# ECG_NEMO_final_V1B_main_stack2.net
KiCad netlist of a schematic drawn in Altium Designer
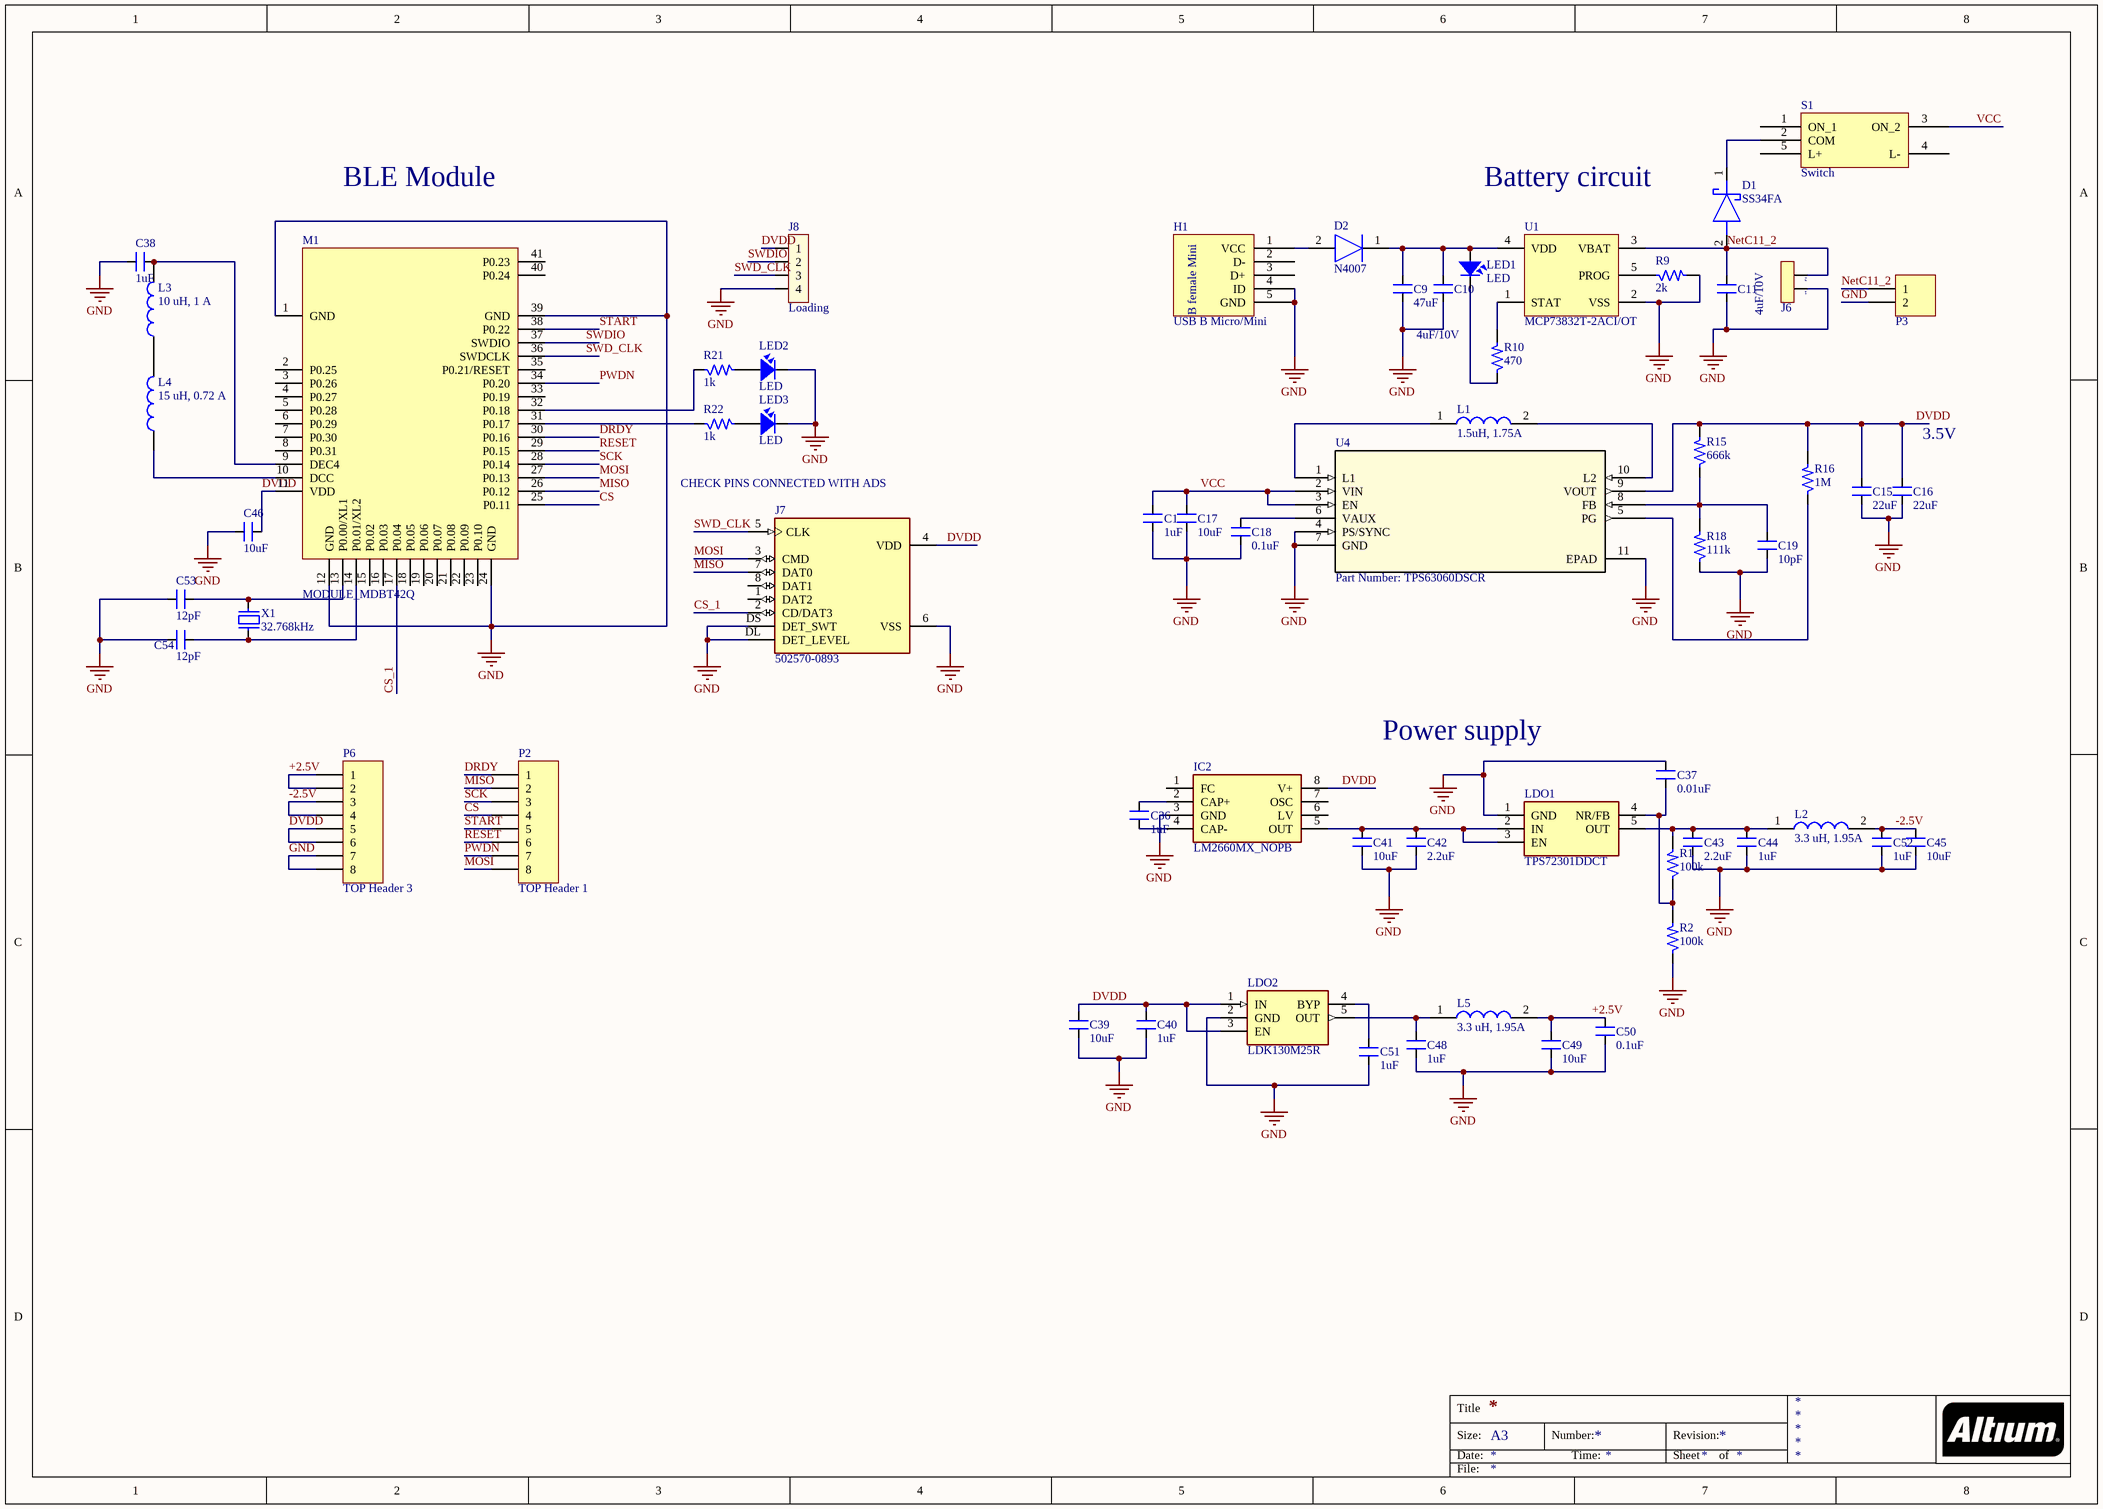
[diagram p0: ECG_NEMO_final_V1B_main_stack2.schdoc]

(export (version "E")
  (design (tool "Eeschema 10.0.6"))
  (components
    (comp (ref "C1")
      (value "1uF")
      (footprint "SM-0805")
      (description "Cap SMD")
      (libsource (lib "VioletofSun") (part "CM"))
    )
    (comp (ref "C9")
      (value "47uF")
      (footprint "SM-0805")
      (description "Cap SMD")
      (libsource (lib "VioletofSun") (part "CM"))
    )
    (comp (ref "C10")
      (value "4uF/10V")
      (footprint "SM-0805")
      (description "Cap SMD")
      (libsource (lib "VioletofSun") (part "CM"))
    )
    (comp (ref "C11")
      (value "4uF/10V")
      (footprint "SM-0805")
      (description "Cap SMD")
      (libsource (lib "VioletofSun") (part "CM"))
    )
    (comp (ref "C15")
      (value "22uF")
      (footprint "SM-0805")
      (description "Cap SMD")
      (libsource (lib "VioletofSun") (part "CM"))
    )
    (comp (ref "C16")
      (value "22uF")
      (footprint "SM-0805")
      (description "Cap SMD")
      (libsource (lib "VioletofSun") (part "CM"))
    )
    (comp (ref "C17")
      (value "10uF")
      (footprint "SM-0805")
      (description "Cap SMD")
      (libsource (lib "VioletofSun") (part "CM"))
    )
    (comp (ref "C18")
      (value "0.1uF")
      (footprint "SM-0805")
      (description "Cap SMD")
      (libsource (lib "VioletofSun") (part "CM"))
    )
    (comp (ref "C19")
      (value "10pF")
      (footprint "SM-0805")
      (description "Cap SMD")
      (libsource (lib "VioletofSun") (part "CM"))
    )
    (comp (ref "C36")
      (value "1uF")
      (footprint "SM-0805")
      (description "Cap SMD")
      (libsource (lib "VioletofSun") (part "CM"))
    )
    (comp (ref "C37")
      (value "0.01uF")
      (footprint "SM-0805")
      (description "Cap SMD")
      (libsource (lib "VioletofSun") (part "CM"))
    )
    (comp (ref "C38")
      (value "1uF")
      (footprint "SM-0805")
      (description "Cap SMD")
      (libsource (lib "VioletofSun") (part "CM"))
    )
    (comp (ref "C39")
      (value "10uF")
      (footprint "SM-0805")
      (description "Cap SMD")
      (libsource (lib "VioletofSun") (part "CM"))
    )
    (comp (ref "C40")
      (value "1uF")
      (footprint "SM-0805")
      (description "Cap SMD")
      (libsource (lib "VioletofSun") (part "CM"))
    )
    (comp (ref "C41")
      (value "10uF")
      (footprint "SM-0805")
      (description "Cap SMD")
      (libsource (lib "VioletofSun") (part "CM"))
    )
    (comp (ref "C42")
      (value "2.2uF")
      (footprint "SM-0805")
      (description "Cap SMD")
      (libsource (lib "VioletofSun") (part "CM"))
    )
    (comp (ref "C43")
      (value "2.2uF")
      (footprint "SM-0805")
      (description "Cap SMD")
      (libsource (lib "VioletofSun") (part "CM"))
    )
    (comp (ref "C44")
      (value "1uF")
      (footprint "SM-0805")
      (description "Cap SMD")
      (libsource (lib "VioletofSun") (part "CM"))
    )
    (comp (ref "C45")
      (value "10uF")
      (footprint "SM-0805")
      (description "Cap SMD")
      (libsource (lib "VioletofSun") (part "CM"))
    )
    (comp (ref "C46")
      (value "10uF")
      (footprint "SM-0805")
      (description "Cap SMD")
      (libsource (lib "VioletofSun") (part "CM"))
    )
    (comp (ref "C48")
      (value "1uF")
      (footprint "SM-0805")
      (description "Cap SMD")
      (libsource (lib "VioletofSun") (part "CM"))
    )
    (comp (ref "C49")
      (value "10uF")
      (footprint "SM-0805")
      (description "Cap SMD")
      (libsource (lib "VioletofSun") (part "CM"))
    )
    (comp (ref "C50")
      (value "0.1uF")
      (footprint "SM-0805")
      (description "Cap SMD")
      (libsource (lib "VioletofSun") (part "CM"))
    )
    (comp (ref "C51")
      (value "1uF")
      (footprint "SM-0805")
      (description "Cap SMD")
      (libsource (lib "VioletofSun") (part "CM"))
    )
    (comp (ref "C52")
      (value "1uF")
      (footprint "SM-0805")
      (description "Cap SMD")
      (libsource (lib "VioletofSun") (part "CM"))
    )
    (comp (ref "C53")
      (value "12pF")
      (footprint "SM-0805")
      (description "Cap SMD")
      (libsource (lib "VioletofSun") (part "CM"))
    )
    (comp (ref "C54")
      (value "12pF")
      (footprint "SM-0805")
      (description "Cap SMD")
      (libsource (lib "VioletofSun") (part "CM"))
    )
    (comp (ref "D1")
      (value "SS34FA")
      (footprint "SODFL3618X143N")
      (description "Schottky Diode")
      (fields (field (name "MOUSER PART NUMBER") "512-SS34FA"))
      (libsource (lib "*") (part "SS34FA"))
    )
    (comp (ref "D2")
      (value "N4007")
      (footprint "DIOM5025X220N")
      (description "Diode")
      (fields
        (field (name "MOUSER PART NUMBER") "346-EC11FS2")
        (field (name "MANUFACTURER_PART_NUMBER") "EC11FS2")
      )
      (libsource (lib "*") (part "EC11FS2"))
    )
    (comp (ref "H1")
      (value "USB B Micro/Mini")
      (footprint "USB-B-MICRO-female Tai02")
      (description "USB B Female Micro/Mini SMD")
      (libsource (lib "mylib") (part "USB B Female Micro/Mini SMD"))
    )
    (comp (ref "IC2")
      (value "LM2660MX_NOPB")
      (footprint "LM2660MX:SOIC127P600X175-8N")
      (description "Integrated Circuit")
      (fields (field (name "MANUFACTURER_PART_NUMBER") "LM2660MX NOPB"))
      (libsource (lib "LM2660MX") (part "LM2660MX_NOPB"))
    )
    (comp (ref "J6")
      (value "Jumper 2")
      (footprint "J2_Jst SH_1mm")
      (libsource (lib "VioletofSun") (part "JP 2"))
    )
    (comp (ref "J7")
      (value "502570-0893")
      (footprint "MOLEX_502570-0893")
      (description "10 _8 + 2_ Position Card Connector Secure Digital - microSDâ„¢ Surface Mount, Right Angle Gold")
      (fields (field (name "MF") "Molex"))
      (libsource (lib "502570-0893") (part "502570-0893"))
    )
    (comp (ref "J8")
      (value "Loading")
      (footprint "sip4")
      (description "Connector 4")
      (libsource (lib "VioletofSun") (part "JP4"))
    )
    (comp (ref "L1")
      (value "1.5uH, 1.75A")
      (footprint "744031001:WE-TPC_381692")
      (description "Inductor")
      (fields
        (field (name "MANUFACTURER_PART_NUMBER") "744031001")
        (field (name "MOUSER PART NUMBER") "710-744031001")
      )
      (libsource (lib "744031001") (part "744031001"))
    )
    (comp (ref "L2")
      (value "3.3 uH, 1.95A")
      (footprint "Inductor-744042003:WE-TPC_4818/482892")
      (description "Inductor")
      (fields
        (field (name "MANUFACTURER_PART_NUMBER") "744042003")
        (field (name "MOUSER PART NUMBER") "710-744042003")
      )
      (libsource (lib "Inductor-744042003") (part "744042003"))
    )
    (comp (ref "L3")
      (value "10 uH, 1 A")
      (footprint "WE-TPC_2828")
      (description "SMT Shielded Tiny Power Inductor WE-TPC, size 2828, 10 uH, 1 A")
      (fields (field (name "PART NUMBER") "744025100") (field (name "PUBLISHER") "Wurth Elektronik"))
      (libsource (lib "ALTIUM-WE-TPC-rev18a") (part "744025100"))
    )
    (comp (ref "L4")
      (value "15 uH, 0.72 A")
      (footprint "WE-TPC_2828")
      (description "SMT Shielded Tiny Power Inductor WE-TPC, size 2828, 15 uH, 0.72 A")
      (fields (field (name "PART NUMBER") "744025150") (field (name "PUBLISHER") "Wurth Elektronik"))
      (libsource (lib "ALTIUM-WE-TPC-rev18a") (part "744025150"))
    )
    (comp (ref "L5")
      (value "3.3 uH, 1.95A")
      (footprint "Inductor-744042003:WE-TPC_4818/482892")
      (description "Inductor")
      (fields
        (field (name "MANUFACTURER_PART_NUMBER") "744042003")
        (field (name "MOUSER PART NUMBER") "710-744042003")
      )
      (libsource (lib "Inductor-744042003") (part "744042003"))
    )
    (comp (ref "LDO1")
      (value "TPS72301DDCT")
      (footprint "TPS72301DDCT:SOT95P280X110-5N")
      (description "Integrated Circuit")
      (fields (field (name "MOUSER PART NUMBER") "595-TPS72301DDCT"))
      (libsource (lib "TPS72301DDCT") (part "TPS72301DDCT"))
    )
    (comp (ref "LDO2")
      (value "LDK130M25R")
      (footprint "LDK130M25R:SOT95P280X145-5N")
      (description "Integrated Circuit")
      (fields (field (name "MOUSER PART NUMBER") "511-LDK130M25R"))
      (libsource (lib "LDK130M25R") (part "LDK130M25R"))
    )
    (comp (ref "LED1")
      (value "LED")
      (footprint "SM-0805")
      (description "LED Single colour Green and Red")
      (libsource (lib "") (part "LED_1"))
    )
    (comp (ref "LED2")
      (value "LED")
      (footprint "led0805")
      (description "LED Single colour Green and Red")
      (libsource (lib "VioletofSun") (part "LED"))
    )
    (comp (ref "LED3")
      (value "LED")
      (footprint "led0805")
      (description "LED Single colour Green and Red")
      (libsource (lib "VioletofSun") (part "LED"))
    )
    (comp (ref "M1")
      (value "MODULE_MDBT42Q")
      (footprint "PCB_MDBT42Q_10X16")
      (description "MDBT42Q")
      (libsource (lib "MDBT42Q_SCHLIB_181015") (part "MODULE_MDBT42Q"))
    )
    (comp (ref "P2")
      (value "TOP Header 1")
      (footprint "HDR1X8")
      (description "Header, 8-Pin")
      (fields (field (name "PUBLISHER") "Altium Limited"))
      (libsource (lib "PCB_NEMO_final_V1B") (part "Header 8"))
    )
    (comp (ref "P3")
      (value "Header 2")
      (footprint "JP2")
      (description "Header, 2-Pin")
      (fields (field (name "PUBLISHER") "Altium Limited"))
      (libsource (lib "PCB_NEMO_final_V1B") (part "Header 2"))
    )
    (comp (ref "P6")
      (value "TOP Header 3")
      (footprint "HDR1X8")
      (description "Header, 8-Pin")
      (fields (field (name "PUBLISHER") "Altium Limited"))
      (libsource (lib "PCB_NEMO_final_V1B") (part "Header 8"))
    )
    (comp (ref "R1")
      (value "100k")
      (footprint "SM-0805")
      (description "Resistor 1/4W")
      (libsource (lib "PCB_NEMO_v1-2_v2-1") (part "R"))
    )
    (comp (ref "R2")
      (value "100k")
      (footprint "SM-0805")
      (description "Resistor 1/4W")
      (libsource (lib "PCB_NEMO_v1-2_v2-1") (part "R"))
    )
    (comp (ref "R9")
      (value "2k")
      (footprint "SM-0805")
      (description "Resistor 1/4W")
      (libsource (lib "VioletofSun") (part "R"))
    )
    (comp (ref "R10")
      (value "470")
      (footprint "SM-0805")
      (description "Resistor 1/4W")
      (libsource (lib "VioletofSun") (part "R"))
    )
    (comp (ref "R15")
      (value "666k")
      (footprint "SM-0805")
      (description "Resistor 1/4W")
      (libsource (lib "VioletofSun") (part "R"))
    )
    (comp (ref "R16")
      (value "1M")
      (footprint "SM-0805")
      (description "Resistor 1/4W")
      (libsource (lib "VioletofSun") (part "R"))
    )
    (comp (ref "R18")
      (value "111k")
      (footprint "SM-0805")
      (description "Resistor 1/4W")
      (libsource (lib "VioletofSun") (part "R"))
    )
    (comp (ref "R21")
      (value "1k")
      (footprint "SM-0805")
      (description "Resistor 1/4W")
      (libsource (lib "VioletofSun") (part "R"))
    )
    (comp (ref "R22")
      (value "1k")
      (footprint "SM-0805")
      (description "Resistor 1/4W")
      (libsource (lib "VioletofSun") (part "R"))
    )
    (comp (ref "S1")
      (value "Switch")
      (footprint "SS12SDP2LC")
      (libsource (lib "SS12SDP2LC") (part "SS12SDP2LC"))
    )
    (comp (ref "U1")
      (value "MCP73832T-2ACI/OT")
      (footprint "SOT-23-OT5_N")
      (fields (field (name "PUBLISHER") "Altium Limited"))
      (libsource (lib "Microchip Power Mgt Battery Management") (part "MCP73832T-2ACI/OT"))
    )
    (comp (ref "U4")
      (value "Part Number: TPS63060DSCR")
      (footprint "DSC10_1P70X2P15")
      (description "No Description Available")
      (fields
        (field (name "MANUFACTURER_PART_NUMBER") "TPS63060DSCR")
        (field (name "MANUFACTURER") "Texas Instruments")
        (field (name "COPYRIGHT") "Copyright (C) 2018 Accelerated Designs. All rights reserved")
      )
      (libsource (lib "2019-06-25_17-28-37") (part "TPS63060DSCR"))
    )
    (comp (ref "X1")
      (value "32.768kHz")
      (footprint "Crystal 32.768kHz SMD")
      (description "Crystal For all Crystal 2pin.")
      (libsource (lib "mylib") (part "Crystal"))
    )
  )
  (nets
    (net (code "1") (name "/+2.5V") (class "Default")
      (node (ref "C49") (pin "2") (pinfunction "2_2") (pintype "passive"))
      (node (ref "C50") (pin "2") (pinfunction "2_2") (pintype "passive"))
      (node (ref "L5") (pin "2") (pinfunction "2_2") (pintype "passive"))
      (node (ref "P6") (pin "1") (pinfunction "1_1") (pintype "passive"))
      (node (ref "P6") (pin "2") (pinfunction "2_2") (pintype "passive"))
    )
    (net (code "2") (name "/-2.5V") (class "Default")
      (node (ref "C45") (pin "2") (pinfunction "2_2") (pintype "passive"))
      (node (ref "C52") (pin "2") (pinfunction "2_2") (pintype "passive"))
      (node (ref "L2") (pin "2") (pinfunction "2_2") (pintype "passive"))
      (node (ref "P6") (pin "3") (pinfunction "3_3") (pintype "passive"))
      (node (ref "P6") (pin "4") (pinfunction "4_4") (pintype "passive"))
    )
    (net (code "3") (name "/CS") (class "Default")
      (node (ref "M1") (pin "25") (pinfunction "P0.11_25") (pintype "passive"))
      (node (ref "P2") (pin "4") (pinfunction "4_4") (pintype "passive"))
    )
    (net (code "4") (name "/CS_1") (class "Default")
      (node (ref "J7") (pin "2") (pinfunction "CD/DAT3_2") (pintype "bidirectional"))
      (node (ref "M1") (pin "17") (pinfunction "P0.04_17") (pintype "passive"))
    )
    (net (code "5") (name "/DRDY") (class "Default")
      (node (ref "M1") (pin "30") (pinfunction "P0.16_30") (pintype "passive"))
      (node (ref "P2") (pin "1") (pinfunction "1_1") (pintype "passive"))
    )
    (net (code "6") (name "/DVDD") (class "Default")
      (node (ref "C15") (pin "2") (pinfunction "2_2") (pintype "passive"))
      (node (ref "C16") (pin "2") (pinfunction "2_2") (pintype "passive"))
      (node (ref "C39") (pin "2") (pinfunction "2_2") (pintype "passive"))
      (node (ref "C40") (pin "2") (pinfunction "2_2") (pintype "passive"))
      (node (ref "C46") (pin "2") (pinfunction "2_2") (pintype "passive"))
      (node (ref "IC2") (pin "8") (pinfunction "V+_8") (pintype "passive"))
      (node (ref "J7") (pin "4") (pinfunction "VDD_4") (pintype "power_in"))
      (node (ref "J8") (pin "1") (pinfunction "1_1") (pintype "passive"))
      (node (ref "LDO2") (pin "1") (pinfunction "IN_1") (pintype "input"))
      (node (ref "LDO2") (pin "3") (pinfunction "EN_3") (pintype "passive"))
      (node (ref "M1") (pin "11") (pinfunction "VDD_11") (pintype "passive"))
      (node (ref "P6") (pin "5") (pinfunction "5_5") (pintype "passive"))
      (node (ref "P6") (pin "6") (pinfunction "6_6") (pintype "passive"))
      (node (ref "R15") (pin "2") (pinfunction "2_2") (pintype "passive"))
      (node (ref "R16") (pin "2") (pinfunction "2_2") (pintype "passive"))
      (node (ref "U4") (pin "9") (pinfunction "VOUT_9") (pintype "output"))
    )
    (net (code "7") (name "/MISO") (class "Default")
      (node (ref "J7") (pin "7") (pinfunction "DAT0_7") (pintype "bidirectional"))
      (node (ref "M1") (pin "26") (pinfunction "P0.12_26") (pintype "passive"))
      (node (ref "P2") (pin "2") (pinfunction "2_2") (pintype "passive"))
    )
    (net (code "8") (name "/MOSI") (class "Default")
      (node (ref "J7") (pin "3") (pinfunction "CMD_3") (pintype "bidirectional"))
      (node (ref "M1") (pin "27") (pinfunction "P0.13_27") (pintype "passive"))
      (node (ref "P2") (pin "8") (pinfunction "8_8") (pintype "passive"))
    )
    (net (code "9") (name "/NetC11_2") (class "Default")
      (node (ref "C11") (pin "2") (pinfunction "2_2") (pintype "passive"))
      (node (ref "D1") (pin "2") (pinfunction "A_2") (pintype "passive"))
      (node (ref "J6") (pin "2") (pinfunction "2_2") (pintype "passive"))
      (node (ref "P3") (pin "1") (pinfunction "1_1") (pintype "passive"))
      (node (ref "U1") (pin "3") (pinfunction "VBAT_3") (pintype "power_in"))
    )
    (net (code "10") (name "/PWDN") (class "Default")
      (node (ref "M1") (pin "34") (pinfunction "P0.20_34") (pintype "passive"))
      (node (ref "P2") (pin "7") (pinfunction "7_7") (pintype "passive"))
    )
    (net (code "11") (name "/RESET") (class "Default")
      (node (ref "M1") (pin "29") (pinfunction "P0.15_29") (pintype "passive"))
      (node (ref "P2") (pin "6") (pinfunction "6_6") (pintype "passive"))
    )
    (net (code "12") (name "/SCK") (class "Default")
      (node (ref "M1") (pin "28") (pinfunction "P0.14_28") (pintype "passive"))
      (node (ref "P2") (pin "3") (pinfunction "3_3") (pintype "passive"))
    )
    (net (code "13") (name "/START") (class "Default")
      (node (ref "M1") (pin "38") (pinfunction "P0.22_38") (pintype "passive"))
      (node (ref "P2") (pin "5") (pinfunction "5_5") (pintype "passive"))
    )
    (net (code "14") (name "/SWDIO") (class "Default")
      (node (ref "J8") (pin "2") (pinfunction "2_2") (pintype "passive"))
      (node (ref "M1") (pin "37") (pinfunction "SWDIO_37") (pintype "passive"))
    )
    (net (code "15") (name "/SWD_CLK") (class "Default")
      (node (ref "J7") (pin "5") (pinfunction "CLK_5") (pintype "input"))
      (node (ref "J8") (pin "3") (pinfunction "3_3") (pintype "passive"))
      (node (ref "M1") (pin "36") (pinfunction "SWDCLK_36") (pintype "passive"))
    )
    (net (code "16") (name "/VCC") (class "Default")
      (node (ref "C1") (pin "2") (pinfunction "2_2") (pintype "passive"))
      (node (ref "C17") (pin "2") (pinfunction "2_2") (pintype "passive"))
      (node (ref "S1") (pin "3") (pinfunction "ON_2_3") (pintype "passive"))
      (node (ref "U4") (pin "2") (pinfunction "VIN_2") (pintype "input"))
      (node (ref "U4") (pin "3") (pinfunction "EN_3") (pintype "input"))
    )
    (net (code "17") (name "GND") (class "Default")
      (node (ref "C1") (pin "1") (pinfunction "1_1") (pintype "passive"))
      (node (ref "C10") (pin "1") (pinfunction "1_1") (pintype "passive"))
      (node (ref "C11") (pin "1") (pinfunction "1_1") (pintype "passive"))
      (node (ref "C15") (pin "1") (pinfunction "1_1") (pintype "passive"))
      (node (ref "C16") (pin "1") (pinfunction "1_1") (pintype "passive"))
      (node (ref "C17") (pin "1") (pinfunction "1_1") (pintype "passive"))
      (node (ref "C18") (pin "1") (pinfunction "1_1") (pintype "passive"))
      (node (ref "C19") (pin "1") (pinfunction "1_1") (pintype "passive"))
      (node (ref "C37") (pin "2") (pinfunction "2_2") (pintype "passive"))
      (node (ref "C38") (pin "1") (pinfunction "1_1") (pintype "passive"))
      (node (ref "C39") (pin "1") (pinfunction "1_1") (pintype "passive"))
      (node (ref "C40") (pin "1") (pinfunction "1_1") (pintype "passive"))
      (node (ref "C41") (pin "1") (pinfunction "1_1") (pintype "passive"))
      (node (ref "C42") (pin "1") (pinfunction "1_1") (pintype "passive"))
      (node (ref "C43") (pin "1") (pinfunction "1_1") (pintype "passive"))
      (node (ref "C44") (pin "1") (pinfunction "1_1") (pintype "passive"))
      (node (ref "C45") (pin "1") (pinfunction "1_1") (pintype "passive"))
      (node (ref "C46") (pin "1") (pinfunction "1_1") (pintype "passive"))
      (node (ref "C48") (pin "1") (pinfunction "1_1") (pintype "passive"))
      (node (ref "C49") (pin "1") (pinfunction "1_1") (pintype "passive"))
      (node (ref "C50") (pin "1") (pinfunction "1_1") (pintype "passive"))
      (node (ref "C51") (pin "1") (pinfunction "1_1") (pintype "passive"))
      (node (ref "C52") (pin "1") (pinfunction "1_1") (pintype "passive"))
      (node (ref "C53") (pin "1") (pinfunction "1_1") (pintype "passive"))
      (node (ref "C54") (pin "1") (pinfunction "1_1") (pintype "passive"))
      (node (ref "C9") (pin "1") (pinfunction "1_1") (pintype "passive"))
      (node (ref "H1") (pin "4") (pinfunction "ID_4") (pintype "passive"))
      (node (ref "H1") (pin "5") (pinfunction "GND_5") (pintype "passive"))
      (node (ref "IC2") (pin "3") (pinfunction "GND_3") (pintype "passive"))
      (node (ref "J6") (pin "1") (pinfunction "1_1") (pintype "passive"))
      (node (ref "J7") (pin "6") (pinfunction "VSS_6") (pintype "power_in"))
      (node (ref "J7") (pin "DL") (pinfunction "DET_LEVEL_DL") (pintype "passive"))
      (node (ref "J7") (pin "DS") (pinfunction "DET_SWT_DS") (pintype "passive"))
      (node (ref "J8") (pin "4") (pinfunction "4_4") (pintype "passive"))
      (node (ref "LDO1") (pin "1") (pinfunction "GND_1") (pintype "passive"))
      (node (ref "LDO2") (pin "2") (pinfunction "GND_2") (pintype "power_in"))
      (node (ref "LED2") (pin "K") (pinfunction "K_K") (pintype "passive"))
      (node (ref "LED3") (pin "K") (pinfunction "K_K") (pintype "passive"))
      (node (ref "M1") (pin "1") (pinfunction "GND_1") (pintype "passive"))
      (node (ref "M1") (pin "12") (pinfunction "GND_12") (pintype "passive"))
      (node (ref "M1") (pin "24") (pinfunction "GND_24") (pintype "passive"))
      (node (ref "M1") (pin "39") (pinfunction "GND_39") (pintype "passive"))
      (node (ref "P3") (pin "2") (pinfunction "2_2") (pintype "passive"))
      (node (ref "P6") (pin "7") (pinfunction "7_7") (pintype "passive"))
      (node (ref "P6") (pin "8") (pinfunction "8_8") (pintype "passive"))
      (node (ref "R18") (pin "1") (pinfunction "1_1") (pintype "passive"))
      (node (ref "R2") (pin "1") (pinfunction "1_1") (pintype "passive"))
      (node (ref "R9") (pin "2") (pinfunction "2_2") (pintype "passive"))
      (node (ref "U1") (pin "2") (pinfunction "VSS_2") (pintype "power_in"))
      (node (ref "U4") (pin "11") (pinfunction "EPAD_11") (pintype "passive"))
      (node (ref "U4") (pin "4") (pinfunction "PS/SYNC_4") (pintype "input"))
      (node (ref "U4") (pin "7") (pinfunction "GND_7") (pintype "power_in"))
    )
    (net (code "18") (name "Net-(D1-K)") (class "Default")
      (node (ref "D1") (pin "1") (pinfunction "K_1") (pintype "passive"))
      (node (ref "S1") (pin "2") (pinfunction "COM_2") (pintype "passive"))
    )
    (net (code "19") (name "Net-(D2-A)") (class "Default")
      (node (ref "D2") (pin "2") (pinfunction "A_2") (pintype "passive"))
      (node (ref "H1") (pin "1") (pinfunction "VCC_1") (pintype "passive"))
    )
    (net (code "20") (name "Net-(D2-K)") (class "Default")
      (node (ref "C10") (pin "2") (pinfunction "2_2") (pintype "passive"))
      (node (ref "C9") (pin "2") (pinfunction "2_2") (pintype "passive"))
      (node (ref "D2") (pin "1") (pinfunction "K_1") (pintype "passive"))
      (node (ref "LED1") (pin "1") (pinfunction "1_1") (pintype "passive"))
      (node (ref "U1") (pin "4") (pinfunction "VDD_4") (pintype "power_in"))
    )
    (net (code "21") (name "Net-(IC2-CAP+)") (class "Default")
      (node (ref "C36") (pin "1") (pinfunction "1_1") (pintype "passive"))
      (node (ref "IC2") (pin "2") (pinfunction "CAP+_2") (pintype "passive"))
    )
    (net (code "22") (name "Net-(IC2-CAP-)") (class "Default")
      (node (ref "C36") (pin "2") (pinfunction "2_2") (pintype "passive"))
      (node (ref "IC2") (pin "4") (pinfunction "CAP-_4") (pintype "passive"))
    )
    (net (code "23") (name "Net-(IC2-OUT)") (class "Default")
      (node (ref "C41") (pin "2") (pinfunction "2_2") (pintype "passive"))
      (node (ref "C42") (pin "2") (pinfunction "2_2") (pintype "passive"))
      (node (ref "IC2") (pin "5") (pinfunction "OUT_5") (pintype "passive"))
      (node (ref "LDO1") (pin "2") (pinfunction "IN_2") (pintype "passive"))
      (node (ref "LDO1") (pin "3") (pinfunction "EN_3") (pintype "passive"))
    )
    (net (code "24") (name "Net-(L3-Pad1)") (class "Default")
      (node (ref "L3") (pin "1") (pinfunction "1_1") (pintype "passive"))
      (node (ref "L4") (pin "2") (pinfunction "2_2") (pintype "passive"))
    )
    (net (code "25") (name "Net-(LDO1-NR{slash}FB)") (class "Default")
      (node (ref "C37") (pin "1") (pinfunction "1_1") (pintype "passive"))
      (node (ref "LDO1") (pin "4") (pinfunction "NR/FB_4") (pintype "passive"))
      (node (ref "R1") (pin "1") (pinfunction "1_1") (pintype "passive"))
      (node (ref "R2") (pin "2") (pinfunction "2_2") (pintype "passive"))
    )
    (net (code "26") (name "Net-(LDO1-OUT)") (class "Default")
      (node (ref "C43") (pin "2") (pinfunction "2_2") (pintype "passive"))
      (node (ref "C44") (pin "2") (pinfunction "2_2") (pintype "passive"))
      (node (ref "L2") (pin "1") (pinfunction "1_1") (pintype "passive"))
      (node (ref "LDO1") (pin "5") (pinfunction "OUT_5") (pintype "passive"))
      (node (ref "R1") (pin "2") (pinfunction "2_2") (pintype "passive"))
    )
    (net (code "27") (name "Net-(LDO2-BYP)") (class "Default")
      (node (ref "C51") (pin "2") (pinfunction "2_2") (pintype "passive"))
      (node (ref "LDO2") (pin "4") (pinfunction "BYP_4") (pintype "passive"))
    )
    (net (code "28") (name "Net-(LDO2-OUT)") (class "Default")
      (node (ref "C48") (pin "2") (pinfunction "2_2") (pintype "passive"))
      (node (ref "L5") (pin "1") (pinfunction "1_1") (pintype "passive"))
      (node (ref "LDO2") (pin "5") (pinfunction "OUT_5") (pintype "output"))
    )
    (net (code "29") (name "Net-(LED1-Pad2)") (class "Default")
      (node (ref "LED1") (pin "2") (pinfunction "2_2") (pintype "passive"))
      (node (ref "R10") (pin "1") (pinfunction "1_1") (pintype "passive"))
    )
    (net (code "30") (name "Net-(LED2-PadA)") (class "Default")
      (node (ref "LED2") (pin "A") (pinfunction "A_A") (pintype "passive"))
      (node (ref "R21") (pin "2") (pinfunction "2_2") (pintype "passive"))
    )
    (net (code "31") (name "Net-(LED3-PadA)") (class "Default")
      (node (ref "LED3") (pin "A") (pinfunction "A_A") (pintype "passive"))
      (node (ref "R22") (pin "2") (pinfunction "2_2") (pintype "passive"))
    )
    (net (code "32") (name "Net-(M1-DCC)") (class "Default")
      (node (ref "L4") (pin "1") (pinfunction "1_1") (pintype "passive"))
      (node (ref "M1") (pin "10") (pinfunction "DCC_10") (pintype "passive"))
    )
    (net (code "33") (name "Net-(M1-DEC4)") (class "Default")
      (node (ref "C38") (pin "2") (pinfunction "2_2") (pintype "passive"))
      (node (ref "L3") (pin "2") (pinfunction "2_2") (pintype "passive"))
      (node (ref "M1") (pin "9") (pinfunction "DEC4_9") (pintype "passive"))
    )
    (net (code "34") (name "Net-(M1-P0.00{slash}XL1)") (class "Default")
      (node (ref "C53") (pin "2") (pinfunction "2_2") (pintype "passive"))
      (node (ref "M1") (pin "13") (pinfunction "P0.00/XL1_13") (pintype "passive"))
      (node (ref "X1") (pin "2") (pinfunction "2_2") (pintype "passive"))
    )
    (net (code "35") (name "Net-(M1-P0.01{slash}XL2)") (class "Default")
      (node (ref "C54") (pin "2") (pinfunction "2_2") (pintype "passive"))
      (node (ref "M1") (pin "14") (pinfunction "P0.01/XL2_14") (pintype "passive"))
      (node (ref "X1") (pin "1") (pinfunction "1_1") (pintype "passive"))
    )
    (net (code "36") (name "Net-(M1-P0.17)") (class "Default")
      (node (ref "M1") (pin "31") (pinfunction "P0.17_31") (pintype "passive"))
      (node (ref "R22") (pin "1") (pinfunction "1_1") (pintype "passive"))
    )
    (net (code "37") (name "Net-(M1-P0.18)") (class "Default")
      (node (ref "M1") (pin "32") (pinfunction "P0.18_32") (pintype "passive"))
      (node (ref "R21") (pin "1") (pinfunction "1_1") (pintype "passive"))
    )
    (net (code "38") (name "Net-(U1-PROG)") (class "Default")
      (node (ref "R9") (pin "1") (pinfunction "1_1") (pintype "passive"))
      (node (ref "U1") (pin "5") (pinfunction "PROG_5") (pintype "passive"))
    )
    (net (code "39") (name "Net-(U1-STAT)") (class "Default")
      (node (ref "R10") (pin "2") (pinfunction "2_2") (pintype "passive"))
      (node (ref "U1") (pin "1") (pinfunction "STAT_1") (pintype "open_collector"))
    )
    (net (code "40") (name "Net-(U4-FB)") (class "Default")
      (node (ref "C19") (pin "2") (pinfunction "2_2") (pintype "passive"))
      (node (ref "R15") (pin "1") (pinfunction "1_1") (pintype "passive"))
      (node (ref "R18") (pin "2") (pinfunction "2_2") (pintype "passive"))
      (node (ref "U4") (pin "8") (pinfunction "FB_8") (pintype "input"))
    )
    (net (code "41") (name "Net-(U4-L1)") (class "Default")
      (node (ref "L1") (pin "1") (pinfunction "1_1") (pintype "passive"))
      (node (ref "U4") (pin "1") (pinfunction "L1_1") (pintype "input"))
    )
    (net (code "42") (name "Net-(U4-L2)") (class "Default")
      (node (ref "L1") (pin "2") (pinfunction "2_2") (pintype "passive"))
      (node (ref "U4") (pin "10") (pinfunction "L2_10") (pintype "input"))
    )
    (net (code "43") (name "Net-(U4-PG)") (class "Default")
      (node (ref "R16") (pin "1") (pinfunction "1_1") (pintype "passive"))
      (node (ref "U4") (pin "5") (pinfunction "PG_5") (pintype "output"))
    )
    (net (code "44") (name "Net-(U4-VAUX)") (class "Default")
      (node (ref "C18") (pin "2") (pinfunction "2_2") (pintype "passive"))
      (node (ref "U4") (pin "6") (pinfunction "VAUX_6") (pintype "passive"))
    )
    (net (code "45") (name "unconnected-(H1-D+-Pad3)") (class "Default")
      (node (ref "H1") (pin "3") (pinfunction "D+_3") (pintype "passive"))
    )
    (net (code "46") (name "unconnected-(H1-D--Pad2)") (class "Default")
      (node (ref "H1") (pin "2") (pinfunction "D-_2") (pintype "passive"))
    )
    (net (code "47") (name "unconnected-(IC2-FC-Pad1)") (class "Default")
      (node (ref "IC2") (pin "1") (pinfunction "FC_1") (pintype "passive"))
    )
    (net (code "48") (name "unconnected-(IC2-LV-Pad6)") (class "Default")
      (node (ref "IC2") (pin "6") (pinfunction "LV_6") (pintype "passive"))
    )
    (net (code "49") (name "unconnected-(IC2-OSC-Pad7)") (class "Default")
      (node (ref "IC2") (pin "7") (pinfunction "OSC_7") (pintype "passive"))
    )
    (net (code "50") (name "unconnected-(J7-DAT1-Pad8)") (class "Default")
      (node (ref "J7") (pin "8") (pinfunction "DAT1_8") (pintype "bidirectional"))
    )
    (net (code "51") (name "unconnected-(J7-DAT2-Pad1)") (class "Default")
      (node (ref "J7") (pin "1") (pinfunction "DAT2_1") (pintype "bidirectional"))
    )
    (net (code "52") (name "unconnected-(M1-P0.02-Pad15)") (class "Default")
      (node (ref "M1") (pin "15") (pinfunction "P0.02_15") (pintype "passive"))
    )
    (net (code "53") (name "unconnected-(M1-P0.03-Pad16)") (class "Default")
      (node (ref "M1") (pin "16") (pinfunction "P0.03_16") (pintype "passive"))
    )
    (net (code "54") (name "unconnected-(M1-P0.05-Pad18)") (class "Default")
      (node (ref "M1") (pin "18") (pinfunction "P0.05_18") (pintype "passive"))
    )
    (net (code "55") (name "unconnected-(M1-P0.06-Pad19)") (class "Default")
      (node (ref "M1") (pin "19") (pinfunction "P0.06_19") (pintype "passive"))
    )
    (net (code "56") (name "unconnected-(M1-P0.07-Pad20)") (class "Default")
      (node (ref "M1") (pin "20") (pinfunction "P0.07_20") (pintype "passive"))
    )
    (net (code "57") (name "unconnected-(M1-P0.08-Pad21)") (class "Default")
      (node (ref "M1") (pin "21") (pinfunction "P0.08_21") (pintype "passive"))
    )
    (net (code "58") (name "unconnected-(M1-P0.09-Pad22)") (class "Default")
      (node (ref "M1") (pin "22") (pinfunction "P0.09_22") (pintype "passive"))
    )
    (net (code "59") (name "unconnected-(M1-P0.10-Pad23)") (class "Default")
      (node (ref "M1") (pin "23") (pinfunction "P0.10_23") (pintype "passive"))
    )
    (net (code "60") (name "unconnected-(M1-P0.19-Pad33)") (class "Default")
      (node (ref "M1") (pin "33") (pinfunction "P0.19_33") (pintype "passive"))
    )
    (net (code "61") (name "unconnected-(M1-P0.21{slash}RESET-Pad35)") (class "Default")
      (node (ref "M1") (pin "35") (pinfunction "P0.21/RESET_35") (pintype "passive"))
    )
    (net (code "62") (name "unconnected-(M1-P0.23-Pad41)") (class "Default")
      (node (ref "M1") (pin "41") (pinfunction "P0.23_41") (pintype "passive"))
    )
    (net (code "63") (name "unconnected-(M1-P0.24-Pad40)") (class "Default")
      (node (ref "M1") (pin "40") (pinfunction "P0.24_40") (pintype "passive"))
    )
    (net (code "64") (name "unconnected-(M1-P0.25-Pad2)") (class "Default")
      (node (ref "M1") (pin "2") (pinfunction "P0.25_2") (pintype "passive"))
    )
    (net (code "65") (name "unconnected-(M1-P0.26-Pad3)") (class "Default")
      (node (ref "M1") (pin "3") (pinfunction "P0.26_3") (pintype "passive"))
    )
    (net (code "66") (name "unconnected-(M1-P0.27-Pad4)") (class "Default")
      (node (ref "M1") (pin "4") (pinfunction "P0.27_4") (pintype "passive"))
    )
    (net (code "67") (name "unconnected-(M1-P0.28-Pad5)") (class "Default")
      (node (ref "M1") (pin "5") (pinfunction "P0.28_5") (pintype "passive"))
    )
    (net (code "68") (name "unconnected-(M1-P0.29-Pad6)") (class "Default")
      (node (ref "M1") (pin "6") (pinfunction "P0.29_6") (pintype "passive"))
    )
    (net (code "69") (name "unconnected-(M1-P0.30-Pad7)") (class "Default")
      (node (ref "M1") (pin "7") (pinfunction "P0.30_7") (pintype "passive"))
    )
    (net (code "70") (name "unconnected-(M1-P0.31-Pad8)") (class "Default")
      (node (ref "M1") (pin "8") (pinfunction "P0.31_8") (pintype "passive"))
    )
    (net (code "71") (name "unconnected-(S1-L+-Pad5)") (class "Default")
      (node (ref "S1") (pin "5") (pinfunction "L+_5") (pintype "passive"))
    )
    (net (code "72") (name "unconnected-(S1-L--Pad4)") (class "Default")
      (node (ref "S1") (pin "4") (pinfunction "L-_4") (pintype "passive"))
    )
    (net (code "73") (name "unconnected-(S1-ON_1-Pad1)") (class "Default")
      (node (ref "S1") (pin "1") (pinfunction "ON_1_1") (pintype "passive"))
    )
  )
)
